# ft232.net
KiCad netlist of a schematic drawn in Altium Designer
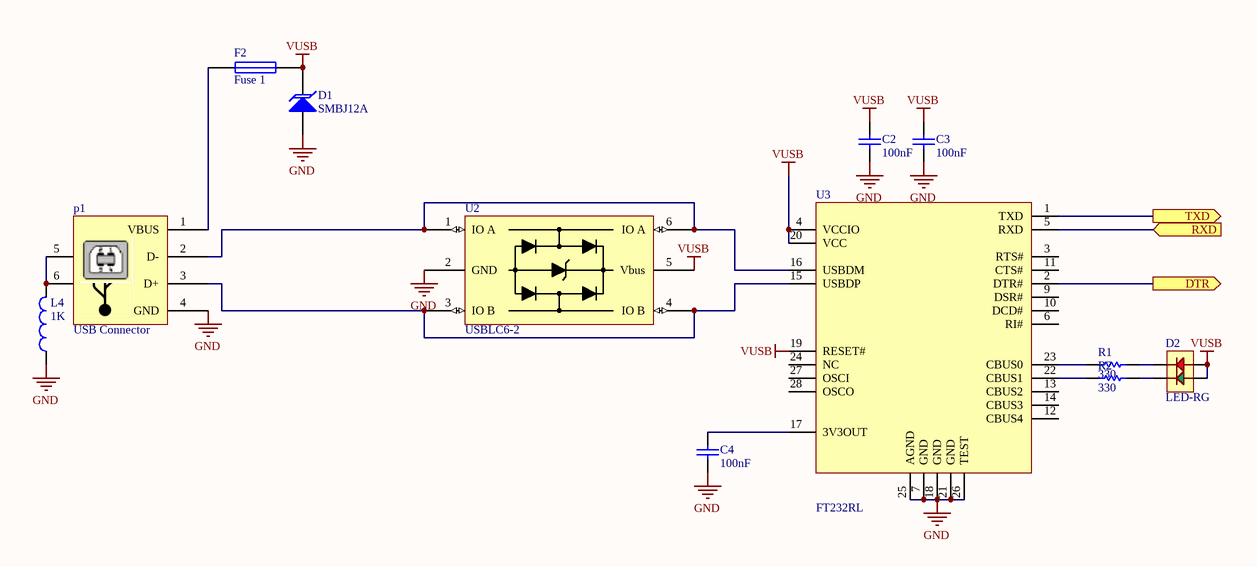
[diagram p0: ft232.SchDoc]

(export (version "E")
  (design (tool "Eeschema 10.0.6"))
  (components
    (comp (ref "C2")
      (value "100nF")
      (footprint "c603")
      (description "Capacitor")
      (fields (field (name "DESIGNER") "Parsa Malekpour"))
      (libsource (lib "ParsaLibrary") (part "Cap"))
    )
    (comp (ref "C3")
      (value "100nF")
      (footprint "c603")
      (description "Capacitor")
      (fields (field (name "DESIGNER") "Parsa Malekpour"))
      (libsource (lib "ParsaLibrary") (part "Cap"))
    )
    (comp (ref "C4")
      (value "100nF")
      (footprint "c603")
      (description "Capacitor")
      (fields (field (name "DESIGNER") "Parsa Malekpour"))
      (libsource (lib "ParsaLibrary") (part "Cap"))
    )
    (comp (ref "D1")
      (value "SMBJ12A")
      (footprint "DO-214AA")
      (description "Surface Mount Transient Voltage Suppressors Diode")
      (libsource (lib "ParsaLibrary") (part "SMBJxxA"))
    )
    (comp (ref "D2")
      (value "LED-RG")
      (footprint "LED-1210")
      (libsource (lib "ParsaLibrary") (part "LED-RG-4"))
    )
    (comp (ref "F2")
      (value "Fuse 1")
      (footprint "PTC-0805")
      (description "Fuse")
      (fields (field (name "PUBLISHER") "Altium Limited"))
      (libsource (lib "Miscellaneous Devices") (part "Fuse 1"))
    )
    (comp (ref "L4")
      (value "1K")
      (footprint "r805")
      (description "FERRITE BEAD")
      (fields (field (name "PUBLISHER") "Altium Limited"))
      (libsource (lib "ParsaLibrary") (part "Ferrite Bead"))
    )
    (comp (ref "p1")
      (value "USB Connector")
      (footprint "USB2-B-R")
      (description "USB Connector-B Type")
      (fields (field (name "DESIGNER") "Eng. Saeid Jorablo"))
      (libsource (lib "ParsaLibrary") (part "USB2-B"))
    )
    (comp (ref "R1")
      (value "330")
      (footprint "R0603")
      (description "Resistor")
      (fields (field (name "DESIGNER") "Parsa Malekpour"))
      (libsource (lib "ParsaLibrary") (part "Resistor"))
    )
    (comp (ref "R2")
      (value "330")
      (footprint "R0603")
      (description "Resistor")
      (fields (field (name "DESIGNER") "Parsa Malekpour"))
      (libsource (lib "ParsaLibrary") (part "Resistor"))
    )
    (comp (ref "U2")
      (value "USBLC6-2")
      (footprint "SOT-23-6")
      (description "Very low capacitance ESD protection")
      (libsource (lib "ParsaLibrary") (part "USBLC6-2"))
    )
    (comp (ref "U3")
      (value "FT232RL")
      (footprint "SSOP-28N")
      (libsource (lib "ParsaLibrary") (part "FT232RL"))
    )
  )
  (nets
    (net (code "1") (name "/DTR") (class "Default")
      (node (ref "U3") (pin "2") (pinfunction "DTR#_2") (pintype "passive"))
    )
    (net (code "2") (name "/RXD") (class "Default")
      (node (ref "U3") (pin "5") (pinfunction "RXD_5") (pintype "passive"))
    )
    (net (code "3") (name "/TXD") (class "Default")
      (node (ref "U3") (pin "1") (pinfunction "TXD_1") (pintype "passive"))
    )
    (net (code "4") (name "GND") (class "Default")
      (node (ref "C2") (pin "1") (pinfunction "1_1") (pintype "passive"))
      (node (ref "C3") (pin "1") (pinfunction "1_1") (pintype "passive"))
      (node (ref "C4") (pin "1") (pinfunction "1_1") (pintype "passive"))
      (node (ref "D1") (pin "1") (pinfunction "A_1") (pintype "passive"))
      (node (ref "L4") (pin "1") (pinfunction "1_1") (pintype "passive"))
      (node (ref "U2") (pin "2") (pinfunction "GND_2") (pintype "power_in"))
      (node (ref "U3") (pin "18") (pinfunction "GND_18") (pintype "passive"))
      (node (ref "U3") (pin "21") (pinfunction "GND_21") (pintype "passive"))
      (node (ref "U3") (pin "25") (pinfunction "AGND_25") (pintype "passive"))
      (node (ref "U3") (pin "26") (pinfunction "TEST_26") (pintype "passive"))
      (node (ref "U3") (pin "7") (pinfunction "GND_7") (pintype "passive"))
      (node (ref "p1") (pin "4") (pinfunction "GND_4") (pintype "power_in"))
    )
    (net (code "5") (name "Net-(D2-GRN-C)") (class "Default")
      (node (ref "D2") (pin "4") (pinfunction "GRN-C_4") (pintype "passive"))
      (node (ref "R2") (pin "2") (pinfunction "2_2") (pintype "passive"))
    )
    (net (code "6") (name "Net-(D2-RED-C)") (class "Default")
      (node (ref "D2") (pin "3") (pinfunction "RED-C_3") (pintype "passive"))
      (node (ref "R1") (pin "2") (pinfunction "2_2") (pintype "passive"))
    )
    (net (code "7") (name "Net-(L4-Pad2)") (class "Default")
      (node (ref "L4") (pin "2") (pinfunction "2_2") (pintype "passive"))
      (node (ref "p1") (pin "5") (pinfunction "5_5") (pintype "passive"))
      (node (ref "p1") (pin "6") (pinfunction "6_6") (pintype "passive"))
    )
    (net (code "8") (name "Net-(U3-3V3OUT)") (class "Default")
      (node (ref "C4") (pin "2") (pinfunction "2_2") (pintype "passive"))
      (node (ref "U3") (pin "17") (pinfunction "3V3OUT_17") (pintype "passive"))
    )
    (net (code "9") (name "Net-(U3-CBUS0)") (class "Default")
      (node (ref "R1") (pin "1") (pinfunction "1_1") (pintype "passive"))
      (node (ref "U3") (pin "23") (pinfunction "CBUS0_23") (pintype "passive"))
    )
    (net (code "10") (name "Net-(U3-CBUS1)") (class "Default")
      (node (ref "R2") (pin "1") (pinfunction "1_1") (pintype "passive"))
      (node (ref "U3") (pin "22") (pinfunction "CBUS1_22") (pintype "passive"))
    )
    (net (code "11") (name "Net-(U3-USBDM)") (class "Default")
      (node (ref "U2") (pin "1") (pinfunction "IO_A_1") (pintype "bidirectional"))
      (node (ref "U2") (pin "6") (pinfunction "IO_A_6") (pintype "bidirectional"))
      (node (ref "U3") (pin "16") (pinfunction "USBDM_16") (pintype "passive"))
      (node (ref "p1") (pin "2") (pinfunction "D-_2") (pintype "passive"))
    )
    (net (code "12") (name "Net-(U3-USBDP)") (class "Default")
      (node (ref "U2") (pin "3") (pinfunction "IO_B_3") (pintype "bidirectional"))
      (node (ref "U2") (pin "4") (pinfunction "IO_B_4") (pintype "bidirectional"))
      (node (ref "U3") (pin "15") (pinfunction "USBDP_15") (pintype "passive"))
      (node (ref "p1") (pin "3") (pinfunction "D+_3") (pintype "passive"))
    )
    (net (code "13") (name "Net-(p1-VBUS)") (class "Default")
      (node (ref "F2") (pin "1") (pinfunction "1_1") (pintype "passive"))
      (node (ref "p1") (pin "1") (pinfunction "VBUS_1") (pintype "power_in"))
    )
    (net (code "14") (name "VUSB") (class "Default")
      (node (ref "C2") (pin "2") (pinfunction "2_2") (pintype "passive"))
      (node (ref "C3") (pin "2") (pinfunction "2_2") (pintype "passive"))
      (node (ref "D1") (pin "2") (pinfunction "K_2") (pintype "passive"))
      (node (ref "D2") (pin "1") (pinfunction "GRN-A_1") (pintype "passive"))
      (node (ref "D2") (pin "2") (pinfunction "RED-A_2") (pintype "passive"))
      (node (ref "F2") (pin "2") (pinfunction "2_2") (pintype "passive"))
      (node (ref "U2") (pin "5") (pinfunction "Vbus_5") (pintype "power_in"))
      (node (ref "U3") (pin "19") (pinfunction "RESET#_19") (pintype "passive"))
      (node (ref "U3") (pin "20") (pinfunction "VCC_20") (pintype "passive"))
      (node (ref "U3") (pin "4") (pinfunction "VCCIO_4") (pintype "passive"))
    )
    (net (code "15") (name "unconnected-(U3-CBUS2-Pad13)") (class "Default")
      (node (ref "U3") (pin "13") (pinfunction "CBUS2_13") (pintype "passive"))
    )
    (net (code "16") (name "unconnected-(U3-CBUS3-Pad14)") (class "Default")
      (node (ref "U3") (pin "14") (pinfunction "CBUS3_14") (pintype "passive"))
    )
    (net (code "17") (name "unconnected-(U3-CBUS4-Pad12)") (class "Default")
      (node (ref "U3") (pin "12") (pinfunction "CBUS4_12") (pintype "passive"))
    )
    (net (code "18") (name "unconnected-(U3-CTS#-Pad11)") (class "Default")
      (node (ref "U3") (pin "11") (pinfunction "CTS#_11") (pintype "passive"))
    )
    (net (code "19") (name "unconnected-(U3-DCD#-Pad10)") (class "Default")
      (node (ref "U3") (pin "10") (pinfunction "DCD#_10") (pintype "passive"))
    )
    (net (code "20") (name "unconnected-(U3-DSR#-Pad9)") (class "Default")
      (node (ref "U3") (pin "9") (pinfunction "DSR#_9") (pintype "passive"))
    )
    (net (code "21") (name "unconnected-(U3-NC-Pad8)") (class "Default")
      (node (ref "U3") (pin "8") (pinfunction "NC_8") (pintype "passive"))
    )
    (net (code "22") (name "unconnected-(U3-NC-Pad24)") (class "Default")
      (node (ref "U3") (pin "24") (pinfunction "NC_24") (pintype "passive"))
    )
    (net (code "23") (name "unconnected-(U3-OSCI-Pad27)") (class "Default")
      (node (ref "U3") (pin "27") (pinfunction "OSCI_27") (pintype "passive"))
    )
    (net (code "24") (name "unconnected-(U3-OSCO-Pad28)") (class "Default")
      (node (ref "U3") (pin "28") (pinfunction "OSCO_28") (pintype "passive"))
    )
    (net (code "25") (name "unconnected-(U3-RI#-Pad6)") (class "Default")
      (node (ref "U3") (pin "6") (pinfunction "RI#_6") (pintype "passive"))
    )
    (net (code "26") (name "unconnected-(U3-RTS#-Pad3)") (class "Default")
      (node (ref "U3") (pin "3") (pinfunction "RTS#_3") (pintype "passive"))
    )
  )
)
